# Voltage_Regulators.net
KiCad netlist of a schematic drawn in Altium Designer
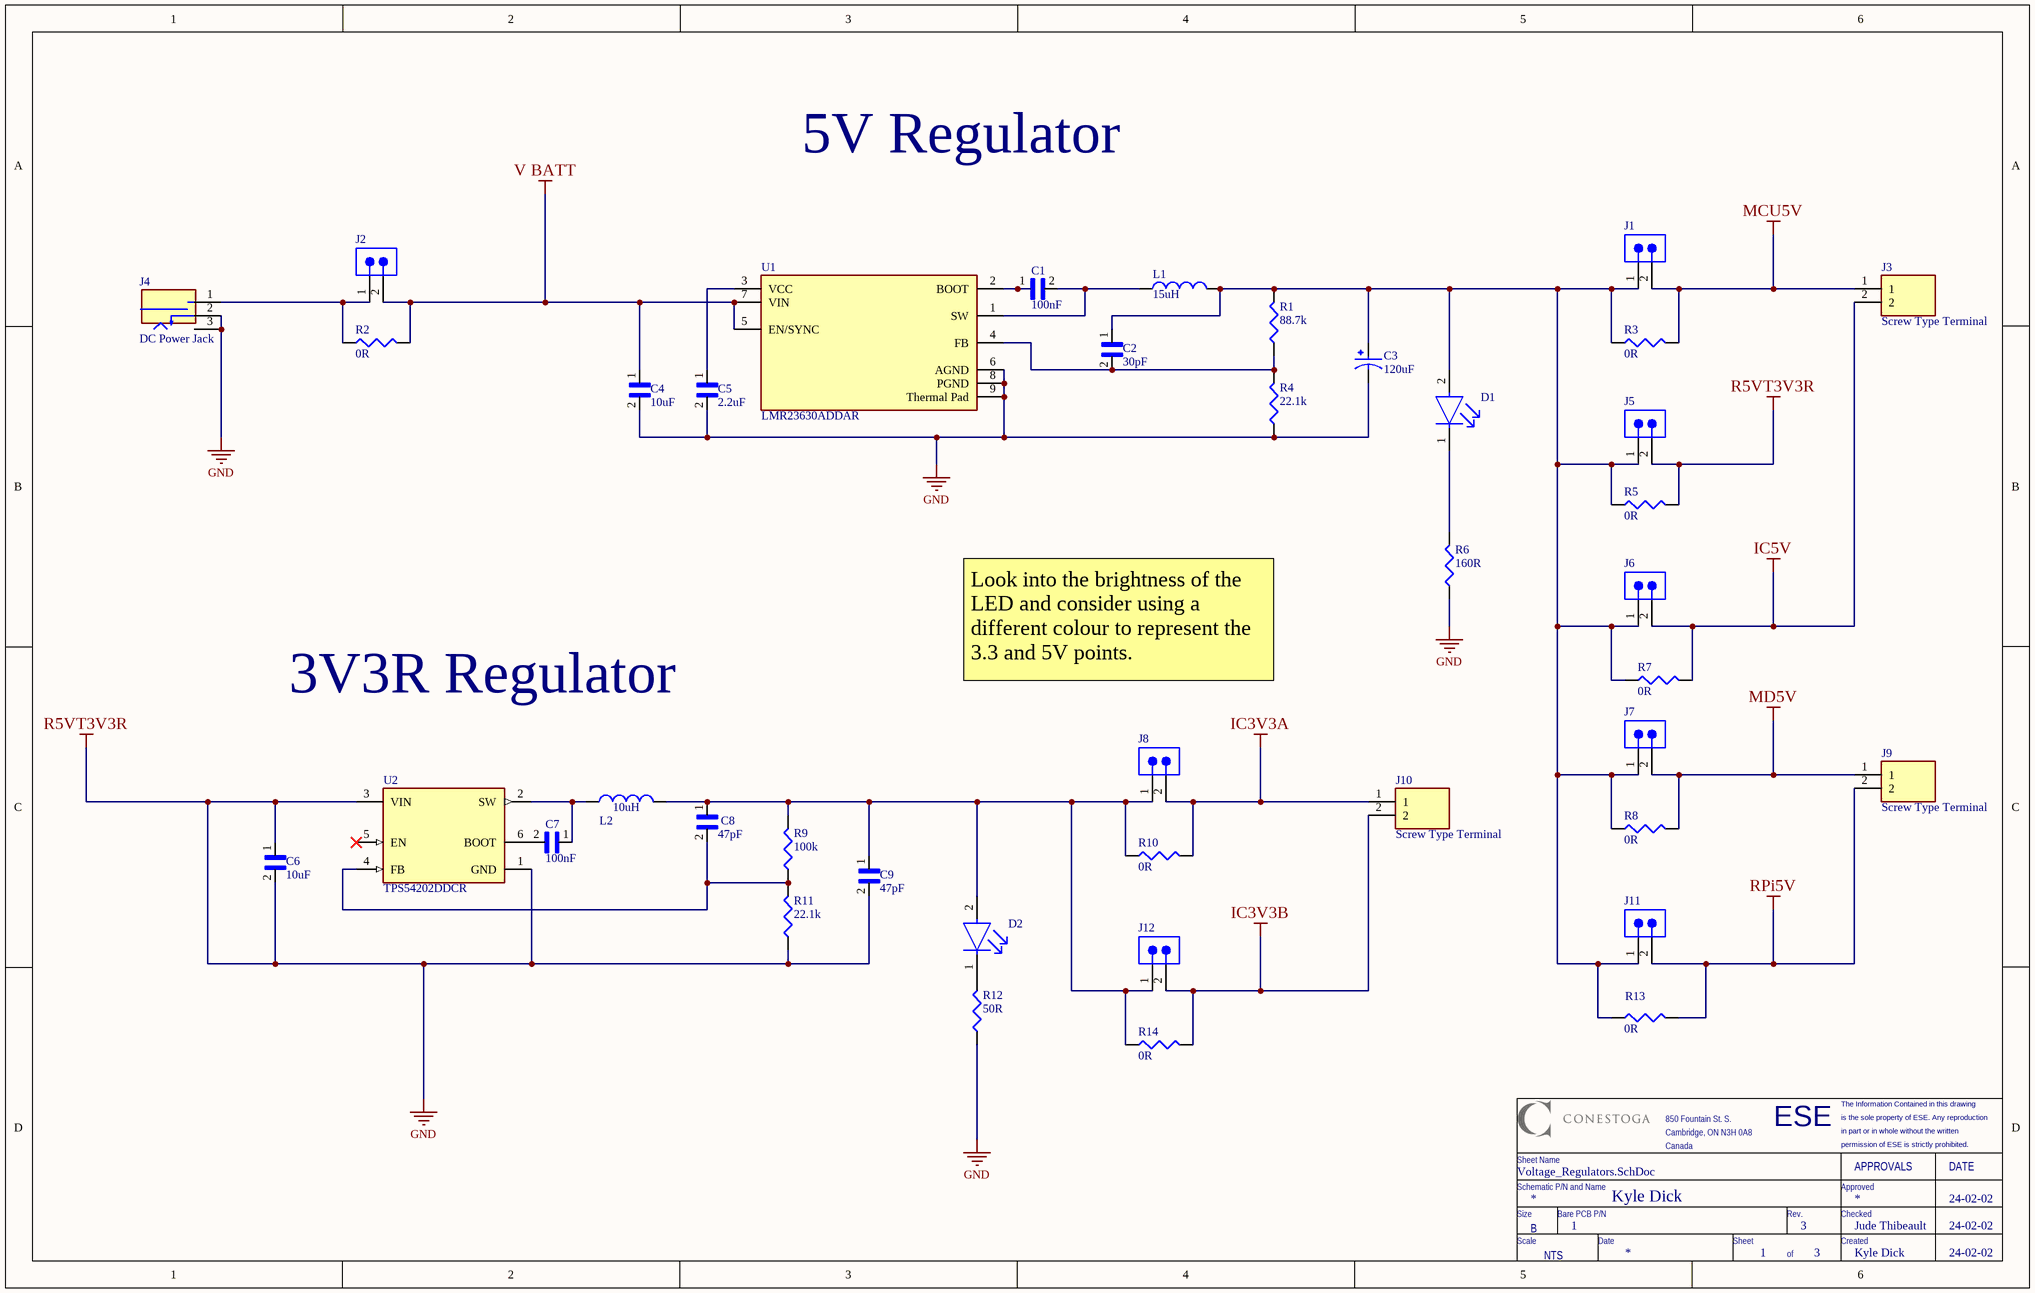
[diagram p0: Voltage_Regulators.SchDoc]

(export (version "E")
  (design (tool "Eeschema 10.0.6"))
  (components
    (comp (ref "C1")
      (value "100nF")
      (footprint "10 uF Cap")
      (description "Ceramic Capacitor 1210")
      (fields (field (name "MF") "Samsung Electro-Mechanics") (field (name "MP") "CL32A106KBJNNNE"))
      (libsource (lib "") (part "Capacitor 0.1uF_1"))
    )
    (comp (ref "C2")
      (value "30pF")
      (footprint "10 uF Cap")
      (description "Ceramic Capacitor 1210")
      (fields (field (name "MF") "Samsung Electro-Mechanics") (field (name "MP") "CL32A106KBJNNNE"))
      (libsource (lib "PCB1") (part "Capacitor 30pF"))
    )
    (comp (ref "C3")
      (value "120uF")
      (footprint "PcbLib1:Capacitor 120uF")
      (description "120 µF 10 V Aluminum - Polymer Capacitors Radial, Can - SMD 27mOhm 2000 Hrs @ 105°C")
      (fields (field (name "MP") "10SVPC120M"))
      (libsource (lib "PCB1") (part "Capacitor 120uF_1"))
    )
    (comp (ref "C4")
      (value "10uF")
      (footprint "10 uF Cap")
      (description "Ceramic Capacitor 1210")
      (fields (field (name "MF") "Samsung Electro-Mechanics") (field (name "MP") "CL32A106KBJNNNE"))
      (libsource (lib "PCB1") (part "Capacitor 10uF"))
    )
    (comp (ref "C5")
      (value "2.2uF")
      (footprint "10 uF Cap")
      (description "Ceramic Capacitor 1210")
      (fields (field (name "MF") "Samsung Electro-Mechanics") (field (name "MP") "CL32A106KBJNNNE"))
      (libsource (lib "PCB1") (part "Capacitor 2.2uF"))
    )
    (comp (ref "C6")
      (value "10uF")
      (footprint "10 uF Cap")
      (description "Ceramic Capacitor 1210")
      (fields (field (name "MF") "Samsung Electro-Mechanics") (field (name "MP") "CL32A106KBJNNNE"))
      (libsource (lib "PCB1") (part "Capacitor 10uF"))
    )
    (comp (ref "C7")
      (value "100nF")
      (footprint "10 uF Cap")
      (description "Ceramic Capacitor 1210")
      (fields (field (name "MF") "Samsung Electro-Mechanics") (field (name "MP") "CL32A106KBJNNNE"))
      (libsource (lib "PCB1") (part "Capacitor 0.1uF"))
    )
    (comp (ref "C8")
      (value "47pF")
      (footprint "10 uF Cap")
      (description "Ceramic Capacitor 1210")
      (fields (field (name "MF") "Samsung Electro-Mechanics") (field (name "MP") "CL32A106KBJNNNE"))
      (libsource (lib "PCB1") (part "Capacitor 47pF"))
    )
    (comp (ref "C9")
      (value "47pF")
      (footprint "10 uF Cap")
      (description "Ceramic Capacitor 1210")
      (fields (field (name "MF") "Samsung Electro-Mechanics") (field (name "MP") "CL32A106KBJNNNE"))
      (libsource (lib "PCB1") (part "Capacitor 47pF"))
    )
    (comp (ref "D1")
      (value "LTST-C190GKT")
      (footprint "FP-LTST-C190GKT-MFG")
      (description "LED GREEN CLEAR CHIP SMD")
      (fields (field (name "VOLTAGE") "2V"))
      (libsource (lib "Altium Content Vault") (part "8706943c75ba83719d021d2fdc84c58"))
    )
    (comp (ref "D2")
      (value "LTST-C190GKT")
      (footprint "FP-LTST-C190GKT-MFG")
      (description "LED GREEN CLEAR CHIP SMD")
      (fields (field (name "VOLTAGE") "2V"))
      (libsource (lib "Altium Content Vault") (part "8706943c75ba83719d021d2fdc84c58"))
    )
    (comp (ref "J1")
      (value "61300211121")
      (footprint "61300211121")
      (libsource (lib "Altium Content Vault") (part "Header_Male_1R_02P"))
    )
    (comp (ref "J2")
      (value "61300211121")
      (footprint "61300211121")
      (libsource (lib "Altium Content Vault") (part "Header_Male_1R_02P"))
    )
    (comp (ref "J3")
      (value "Screw Type Terminal")
      (footprint "2 Pin Terminal Blue Screw")
      (description "2~24 Poles, Screw Type, Horizontal, 5.0 Pitch, 22~12 (AWG), Terminal Block Connector")
      (fields (field (name "MP") "TB002-500-02BE") (field (name "MF") "CUI Devices"))
      (libsource (lib "PCB1") (part "Screw Type Terminal"))
    )
    (comp (ref "J4")
      (value "DC Power Jack")
      (footprint "GRAVITECH_CON-SOCJ-2155")
      (description "DC Power Connectors Power Jack/Connector 2.1mm x 5.5mm")
      (fields (field (name "MF") "Gravitech") (field (name "MP") "CON-SOCJ-2155"))
      (libsource (lib "PCB1") (part "DC Power Jack"))
    )
    (comp (ref "J5")
      (value "61300211121")
      (footprint "61300211121")
      (libsource (lib "Altium Content Vault") (part "Header_Male_1R_02P"))
    )
    (comp (ref "J6")
      (value "61300211121")
      (footprint "61300211121")
      (libsource (lib "Altium Content Vault") (part "Header_Male_1R_02P"))
    )
    (comp (ref "J7")
      (value "61300211121")
      (footprint "61300211121")
      (libsource (lib "Altium Content Vault") (part "Header_Male_1R_02P"))
    )
    (comp (ref "J8")
      (value "61300211121")
      (footprint "61300211121")
      (libsource (lib "Altium Content Vault") (part "Header_Male_1R_02P"))
    )
    (comp (ref "J9")
      (value "Screw Type Terminal")
      (footprint "2 Pin Terminal Blue Screw")
      (description "2~24 Poles, Screw Type, Horizontal, 5.0 Pitch, 22~12 (AWG), Terminal Block Connector")
      (fields (field (name "MP") "TB002-500-02BE") (field (name "MF") "CUI Devices"))
      (libsource (lib "PCB1") (part "Screw Type Terminal"))
    )
    (comp (ref "J10")
      (value "Screw Type Terminal")
      (footprint "2 Pin Terminal Blue Screw")
      (description "2~24 Poles, Screw Type, Horizontal, 5.0 Pitch, 22~12 (AWG), Terminal Block Connector")
      (fields (field (name "MP") "TB002-500-02BE") (field (name "MF") "CUI Devices"))
      (libsource (lib "PCB1") (part "Screw Type Terminal"))
    )
    (comp (ref "J11")
      (value "61300211121")
      (footprint "61300211121")
      (libsource (lib "Altium Content Vault") (part "Header_Male_1R_02P"))
    )
    (comp (ref "J12")
      (value "61300211121")
      (footprint "61300211121")
      (libsource (lib "Altium Content Vault") (part "Header_Male_1R_02P"))
    )
    (comp (ref "L1")
      (value "15uH")
      (footprint "15uH Inductor")
      (description "15 µH Unshielded Wirewound Inductor 4 A 36mOhm Max Nonstandard")
      (libsource (lib "PCB1") (part "Inductor"))
    )
    (comp (ref "L2")
      (value "10uH")
      (footprint "10uH Inductor")
      (description "10 µH Unshielded Wirewound Inductor 2.6 A 60mOhm Max 2424 (6060 Metric)")
      (libsource (lib "PCB1") (part "Inductor_2"))
    )
    (comp (ref "R1")
      (value "88.7k")
      (footprint "RESC2112X05M")
      (description "88.7k 1206 smd")
      (libsource (lib "PCB1") (part "Resistor 88.7k"))
    )
    (comp (ref "R2")
      (value "0R")
      (footprint "RESC2112X05M")
      (description "0R 1206 smd")
      (libsource (lib "PCB1") (part "Resistor 0R"))
    )
    (comp (ref "R3")
      (value "0R")
      (footprint "RESC2112X05M")
      (description "0R 1206 smd")
      (libsource (lib "PCB1") (part "Resistor 0R"))
    )
    (comp (ref "R4")
      (value "22.1k")
      (footprint "RESC2112X05M")
      (description "22.1k 1206 smd")
      (libsource (lib "PCB1") (part "Resistor 22.1k"))
    )
    (comp (ref "R5")
      (value "0R")
      (footprint "RESC2112X05M")
      (description "0R 1206 smd")
      (libsource (lib "PCB1") (part "Resistor 0R"))
    )
    (comp (ref "R6")
      (value "160R")
      (footprint "RESC2112X05M")
      (description "1206 smd")
      (libsource (lib "PCB1") (part "Resistor 160R"))
    )
    (comp (ref "R7")
      (value "0R")
      (footprint "RESC2112X05M")
      (description "0R 1206 smd")
      (libsource (lib "PCB1") (part "Resistor 0R"))
    )
    (comp (ref "R8")
      (value "0R")
      (footprint "RESC2112X05M")
      (description "0R 1206 smd")
      (libsource (lib "PCB1") (part "Resistor 0R"))
    )
    (comp (ref "R9")
      (value "100k")
      (footprint "RESC2112X05M")
      (description "100k 1206 smd")
      (libsource (lib "PCB1") (part "Resistor 100k"))
    )
    (comp (ref "R10")
      (value "0R")
      (footprint "RESC2112X05M")
      (description "0R 1206 smd")
      (libsource (lib "PCB1") (part "Resistor 0R"))
    )
    (comp (ref "R11")
      (value "22.1k")
      (footprint "RESC2112X05M")
      (description "22.1k 1206 smd")
      (libsource (lib "PCB1") (part "Resistor 22.1k"))
    )
    (comp (ref "R12")
      (value "50R")
      (footprint "RESC2112X05M")
      (description "50R 1206 smd")
      (libsource (lib "PCB1") (part "Resistor 50R"))
    )
    (comp (ref "R13")
      (value "0R")
      (footprint "RESC2112X05M")
      (description "0R 1206 smd")
      (libsource (lib "PCB1") (part "Resistor 0R"))
    )
    (comp (ref "R14")
      (value "0R")
      (footprint "RESC2112X05M")
      (description "0R 1206 smd")
      (libsource (lib "PCB1") (part "Resistor 0R"))
    )
    (comp (ref "U1")
      (value "LMR23630ADDAR")
      (footprint "FP-DDA0008E-MFG")
      (description "IC REG BUCK ADJUSTABLE 3A 8SOPWR")
      (libsource (lib "Altium Content Vault") (part "58cfab92c18b1e9607657e2a6918072"))
    )
    (comp (ref "U2")
      (value "TPS54202DDCR")
      (footprint "FP-DDC0006A-IPC_B")
      (description "IC REG BUCK ADJ 2A TSOT23-6")
      (libsource (lib "Altium Content Vault") (part "35c2d3f1afc239a386b2ba50eead654"))
    )
  )
  (nets
    (net (code "1") (name "GND") (class "Default")
      (node (ref "C3") (pin "2") (pinfunction "2_2") (pintype "passive"))
      (node (ref "C4") (pin "2") (pinfunction "2_2") (pintype "passive"))
      (node (ref "C5") (pin "2") (pinfunction "2_2") (pintype "passive"))
      (node (ref "C6") (pin "1") (pinfunction "1_1") (pintype "passive"))
      (node (ref "C6") (pin "2") (pinfunction "2_2") (pintype "passive"))
      (node (ref "C9") (pin "2") (pinfunction "2_2") (pintype "passive"))
      (node (ref "J4") (pin "2") (pinfunction "2_2") (pintype "passive"))
      (node (ref "J4") (pin "3") (pinfunction "3_3") (pintype "passive"))
      (node (ref "J5") (pin "2") (pinfunction "2_2") (pintype "passive"))
      (node (ref "R11") (pin "1") (pinfunction "1_1") (pintype "passive"))
      (node (ref "R12") (pin "1") (pinfunction "1_1") (pintype "passive"))
      (node (ref "R4") (pin "1") (pinfunction "1_1") (pintype "passive"))
      (node (ref "R5") (pin "2") (pinfunction "2_2") (pintype "passive"))
      (node (ref "R6") (pin "1") (pinfunction "1_1") (pintype "passive"))
      (node (ref "U1") (pin "6") (pinfunction "AGND_6") (pintype "power_in"))
      (node (ref "U1") (pin "8") (pinfunction "PGND_8") (pintype "power_in"))
      (node (ref "U1") (pin "9") (pinfunction "Thermal_Pad_9") (pintype "power_in"))
      (node (ref "U2") (pin "1") (pinfunction "GND_1") (pintype "power_in"))
      (node (ref "U2") (pin "3") (pinfunction "VIN_3") (pintype "power_in"))
    )
    (net (code "2") (name "IC3V3A") (class "Default")
      (node (ref "J10") (pin "1") (pinfunction "1_1") (pintype "passive"))
      (node (ref "J8") (pin "2") (pinfunction "2_2") (pintype "passive"))
      (node (ref "R10") (pin "2") (pinfunction "2_2") (pintype "passive"))
    )
    (net (code "3") (name "IC3V3B") (class "Default")
      (node (ref "J10") (pin "2") (pinfunction "2_2") (pintype "passive"))
      (node (ref "J12") (pin "2") (pinfunction "2_2") (pintype "passive"))
      (node (ref "R14") (pin "2") (pinfunction "2_2") (pintype "passive"))
    )
    (net (code "4") (name "IC5V") (class "Default")
      (node (ref "J3") (pin "2") (pinfunction "2_2") (pintype "passive"))
      (node (ref "J6") (pin "2") (pinfunction "2_2") (pintype "passive"))
      (node (ref "R7") (pin "2") (pinfunction "2_2") (pintype "passive"))
    )
    (net (code "5") (name "MCU5V") (class "Default")
      (node (ref "J1") (pin "2") (pinfunction "2_2") (pintype "passive"))
      (node (ref "J3") (pin "1") (pinfunction "1_1") (pintype "passive"))
      (node (ref "R3") (pin "2") (pinfunction "2_2") (pintype "passive"))
    )
    (net (code "6") (name "MD5V") (class "Default")
      (node (ref "J7") (pin "2") (pinfunction "2_2") (pintype "passive"))
      (node (ref "J9") (pin "1") (pinfunction "1_1") (pintype "passive"))
      (node (ref "R8") (pin "2") (pinfunction "2_2") (pintype "passive"))
    )
    (net (code "7") (name "Net-(D1-A)") (class "Default")
      (node (ref "C2") (pin "1") (pinfunction "1_1") (pintype "passive"))
      (node (ref "C3") (pin "1") (pinfunction "1_1") (pintype "passive"))
      (node (ref "D1") (pin "2") (pinfunction "A_2") (pintype "passive"))
      (node (ref "J1") (pin "1") (pinfunction "1_1") (pintype "passive"))
      (node (ref "J11") (pin "1") (pinfunction "1_1") (pintype "passive"))
      (node (ref "J5") (pin "1") (pinfunction "1_1") (pintype "passive"))
      (node (ref "J6") (pin "1") (pinfunction "1_1") (pintype "passive"))
      (node (ref "J7") (pin "1") (pinfunction "1_1") (pintype "passive"))
      (node (ref "L1") (pin "2") (pinfunction "2_2") (pintype "passive"))
      (node (ref "R1") (pin "2") (pinfunction "2_2") (pintype "passive"))
      (node (ref "R13") (pin "1") (pinfunction "1_1") (pintype "passive"))
      (node (ref "R3") (pin "1") (pinfunction "1_1") (pintype "passive"))
      (node (ref "R5") (pin "1") (pinfunction "1_1") (pintype "passive"))
      (node (ref "R7") (pin "1") (pinfunction "1_1") (pintype "passive"))
      (node (ref "R8") (pin "1") (pinfunction "1_1") (pintype "passive"))
    )
    (net (code "8") (name "Net-(D1-C)") (class "Default")
      (node (ref "D1") (pin "1") (pinfunction "C_1") (pintype "passive"))
      (node (ref "R6") (pin "2") (pinfunction "2_2") (pintype "passive"))
    )
    (net (code "9") (name "Net-(D2-A)") (class "Default")
      (node (ref "C8") (pin "1") (pinfunction "1_1") (pintype "passive"))
      (node (ref "C9") (pin "1") (pinfunction "1_1") (pintype "passive"))
      (node (ref "D2") (pin "2") (pinfunction "A_2") (pintype "passive"))
      (node (ref "J12") (pin "1") (pinfunction "1_1") (pintype "passive"))
      (node (ref "J8") (pin "1") (pinfunction "1_1") (pintype "passive"))
      (node (ref "L2") (pin "2") (pinfunction "2_2") (pintype "passive"))
      (node (ref "R10") (pin "1") (pinfunction "1_1") (pintype "passive"))
      (node (ref "R14") (pin "1") (pinfunction "1_1") (pintype "passive"))
      (node (ref "R9") (pin "2") (pinfunction "2_2") (pintype "passive"))
    )
    (net (code "10") (name "Net-(D2-C)") (class "Default")
      (node (ref "D2") (pin "1") (pinfunction "C_1") (pintype "passive"))
      (node (ref "R12") (pin "2") (pinfunction "2_2") (pintype "passive"))
    )
    (net (code "11") (name "Net-(J2-Pad1)") (class "Default")
      (node (ref "J2") (pin "1") (pinfunction "1_1") (pintype "passive"))
      (node (ref "J4") (pin "1") (pinfunction "1_1") (pintype "passive"))
      (node (ref "R2") (pin "1") (pinfunction "1_1") (pintype "passive"))
    )
    (net (code "12") (name "Net-(U1-BOOT)") (class "Default")
      (node (ref "C1") (pin "1") (pinfunction "1_1") (pintype "passive"))
      (node (ref "U1") (pin "2") (pinfunction "BOOT_2") (pintype "passive"))
    )
    (net (code "13") (name "Net-(U1-FB)") (class "Default")
      (node (ref "C2") (pin "2") (pinfunction "2_2") (pintype "passive"))
      (node (ref "R1") (pin "1") (pinfunction "1_1") (pintype "passive"))
      (node (ref "R4") (pin "2") (pinfunction "2_2") (pintype "passive"))
      (node (ref "U1") (pin "4") (pinfunction "FB_4") (pintype "passive"))
    )
    (net (code "14") (name "Net-(U1-SW)") (class "Default")
      (node (ref "C1") (pin "2") (pinfunction "2_2") (pintype "passive"))
      (node (ref "L1") (pin "1") (pinfunction "1_1") (pintype "passive"))
      (node (ref "U1") (pin "1") (pinfunction "SW_1") (pintype "passive"))
    )
    (net (code "15") (name "Net-(U1-VCC)") (class "Default")
      (node (ref "C5") (pin "1") (pinfunction "1_1") (pintype "passive"))
      (node (ref "U1") (pin "3") (pinfunction "VCC_3") (pintype "power_in"))
    )
    (net (code "16") (name "Net-(U2-BOOT)") (class "Default")
      (node (ref "C7") (pin "2") (pinfunction "2_2") (pintype "passive"))
      (node (ref "U2") (pin "6") (pinfunction "BOOT_6") (pintype "passive"))
    )
    (net (code "17") (name "Net-(U2-FB)") (class "Default")
      (node (ref "C8") (pin "2") (pinfunction "2_2") (pintype "passive"))
      (node (ref "R11") (pin "2") (pinfunction "2_2") (pintype "passive"))
      (node (ref "R9") (pin "1") (pinfunction "1_1") (pintype "passive"))
      (node (ref "U2") (pin "4") (pinfunction "FB_4") (pintype "input"))
    )
    (net (code "18") (name "Net-(U2-SW)") (class "Default")
      (node (ref "C7") (pin "1") (pinfunction "1_1") (pintype "passive"))
      (node (ref "L2") (pin "1") (pinfunction "1_1") (pintype "passive"))
      (node (ref "U2") (pin "2") (pinfunction "SW_2") (pintype "output"))
    )
    (net (code "19") (name "RPi5V") (class "Default")
      (node (ref "J11") (pin "2") (pinfunction "2_2") (pintype "passive"))
      (node (ref "J9") (pin "2") (pinfunction "2_2") (pintype "passive"))
      (node (ref "R13") (pin "2") (pinfunction "2_2") (pintype "passive"))
    )
    (net (code "20") (name "V BATT") (class "Default")
      (node (ref "C4") (pin "1") (pinfunction "1_1") (pintype "passive"))
      (node (ref "J2") (pin "2") (pinfunction "2_2") (pintype "passive"))
      (node (ref "R2") (pin "2") (pinfunction "2_2") (pintype "passive"))
      (node (ref "U1") (pin "5") (pinfunction "EN/SYNC_5") (pintype "passive"))
      (node (ref "U1") (pin "7") (pinfunction "VIN_7") (pintype "power_in"))
    )
    (net (code "21") (name "unconnected-(U2-EN-Pad5)") (class "Default")
      (node (ref "U2") (pin "5") (pinfunction "EN_5") (pintype "input+no_connect"))
    )
  )
)
